# depg0213.net
KiCad netlist of a schematic drawn in Altium Designer
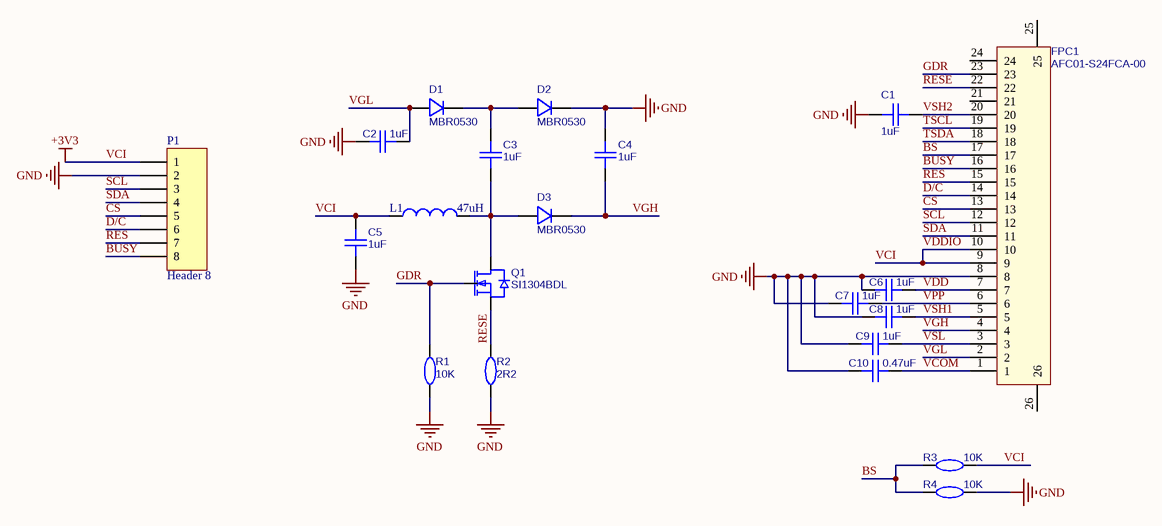
[diagram p0: depg0213.SchDoc]

(export (version "E")
  (design (tool "Eeschema 10.0.6"))
  (components
    (comp (ref "C1")
      (value "1uF")
      (footprint "C0603")
      (fields
        (field (name "BOM_SUPPLIER PART") "C325469")
        (field (name "BOM_MANUFACTURER PART") "CC0603GRNPO9BN200")
        (field (name "CONTRIBUTOR") "LCSC")
      )
      (libsource (lib "miscpcb") (part "CAP_0603"))
    )
    (comp (ref "C2")
      (value "1uF")
      (footprint "C0603")
      (fields
        (field (name "BOM_SUPPLIER PART") "C325469")
        (field (name "BOM_MANUFACTURER PART") "CC0603GRNPO9BN200")
        (field (name "CONTRIBUTOR") "LCSC")
      )
      (libsource (lib "miscpcb") (part "CAP_0603"))
    )
    (comp (ref "C3")
      (value "1uF")
      (footprint "C0603")
      (fields
        (field (name "BOM_SUPPLIER PART") "C325469")
        (field (name "BOM_MANUFACTURER PART") "CC0603GRNPO9BN200")
        (field (name "CONTRIBUTOR") "LCSC")
      )
      (libsource (lib "miscpcb") (part "CAP_0603"))
    )
    (comp (ref "C4")
      (value "1uF")
      (footprint "C0603")
      (fields
        (field (name "BOM_SUPPLIER PART") "C325469")
        (field (name "BOM_MANUFACTURER PART") "CC0603GRNPO9BN200")
        (field (name "CONTRIBUTOR") "LCSC")
      )
      (libsource (lib "miscpcb") (part "CAP_0603"))
    )
    (comp (ref "C5")
      (value "1uF")
      (footprint "C0603")
      (fields
        (field (name "BOM_SUPPLIER PART") "C325469")
        (field (name "BOM_MANUFACTURER PART") "CC0603GRNPO9BN200")
        (field (name "CONTRIBUTOR") "LCSC")
      )
      (libsource (lib "miscpcb") (part "CAP_0603"))
    )
    (comp (ref "C6")
      (value "1uF")
      (footprint "C0603")
      (fields
        (field (name "BOM_SUPPLIER PART") "C325469")
        (field (name "BOM_MANUFACTURER PART") "CC0603GRNPO9BN200")
        (field (name "CONTRIBUTOR") "LCSC")
      )
      (libsource (lib "miscpcb") (part "CAP_0603"))
    )
    (comp (ref "C7")
      (value "1uF")
      (footprint "C0603")
      (fields
        (field (name "BOM_SUPPLIER PART") "C325469")
        (field (name "BOM_MANUFACTURER PART") "CC0603GRNPO9BN200")
        (field (name "CONTRIBUTOR") "LCSC")
      )
      (libsource (lib "miscpcb") (part "CAP_0603"))
    )
    (comp (ref "C8")
      (value "1uF")
      (footprint "C0603")
      (fields
        (field (name "BOM_SUPPLIER PART") "C325469")
        (field (name "BOM_MANUFACTURER PART") "CC0603GRNPO9BN200")
        (field (name "CONTRIBUTOR") "LCSC")
      )
      (libsource (lib "miscpcb") (part "CAP_0603"))
    )
    (comp (ref "C9")
      (value "1uF")
      (footprint "C0603")
      (fields
        (field (name "BOM_SUPPLIER PART") "C325469")
        (field (name "BOM_MANUFACTURER PART") "CC0603GRNPO9BN200")
        (field (name "CONTRIBUTOR") "LCSC")
      )
      (libsource (lib "miscpcb") (part "CAP_0603"))
    )
    (comp (ref "C10")
      (value "0.47uF")
      (footprint "C0603")
      (fields
        (field (name "BOM_SUPPLIER PART") "C325469")
        (field (name "BOM_MANUFACTURER PART") "CC0603GRNPO9BN200")
        (field (name "CONTRIBUTOR") "LCSC")
      )
      (libsource (lib "miscpcb") (part "CAP_0603"))
    )
    (comp (ref "D1")
      (value "MBR0530")
      (footprint "SOD-123_L2.8-W1.8-LS3.7-RD")
      (description "C77336")
      (libsource (lib "miscpcb") (part "MBR0530"))
    )
    (comp (ref "D2")
      (value "MBR0530")
      (footprint "SOD-123_L2.8-W1.8-LS3.7-RD")
      (description "C77336")
      (libsource (lib "miscpcb") (part "MBR0530"))
    )
    (comp (ref "D3")
      (value "MBR0530")
      (footprint "SOD-123_L2.8-W1.8-LS3.7-RD")
      (description "C77336")
      (libsource (lib "miscpcb") (part "MBR0530"))
    )
    (comp (ref "FPC1")
      (value "AFC01-S24FCA-00")
      (footprint "FPC-SMD_P0.50-24P_FGS-XJ-H2.0")
      (description "C262669")
      (fields (field (name "CONTRIBUTOR") "LCSC"))
      (libsource (lib "miscpcb") (part "AFC01-S24FCA-00"))
    )
    (comp (ref "L1")
      (value "47uH")
      (footprint "IND-SMD_L3.0-W3.0_SMNR3015")
      (fields (field (name "PUBLISHER") "Altium Limited"))
      (libsource (lib "Miscellaneous Devices") (part "Inductor"))
    )
    (comp (ref "P1")
      (value "Header 8")
      (footprint "HDR1X8")
      (description "Header, 8-Pin")
      (fields (field (name "PUBLISHER") "Altium Limited"))
      (libsource (lib "Miscellaneous Connectors") (part "Header 8"))
    )
    (comp (ref "Q1")
      (value "SI1304BDL")
      (footprint "SC-70-3_L2.1-W1.3-P1.30-LS2.1-BR")
      (description "C710060")
      (fields (field (name "CONTRIBUTOR") "LCSC"))
      (libsource (lib "miscpcb") (part "SI1304BDL"))
    )
    (comp (ref "R1")
      (value "10K")
      (footprint "R0603")
      (fields
        (field (name "BOM_MANUFACTURER PART") "CR0603JA0301G")
        (field (name "BOM_SUPPLIER PART") "C101323")
      )
      (libsource (lib "miscpcb") (part "RES_0603"))
    )
    (comp (ref "R2")
      (value "2R2")
      (footprint "R0603")
      (fields
        (field (name "BOM_MANUFACTURER PART") "CR0603JA0301G")
        (field (name "BOM_SUPPLIER PART") "C101323")
      )
      (libsource (lib "miscpcb") (part "RES_0603"))
    )
    (comp (ref "R3")
      (value "10K")
      (footprint "R0603")
      (fields
        (field (name "BOM_MANUFACTURER PART") "CR0603JA0301G")
        (field (name "BOM_SUPPLIER PART") "C101323")
      )
      (libsource (lib "miscpcb") (part "RES_0603"))
    )
    (comp (ref "R4")
      (value "10K")
      (footprint "R0603")
      (fields
        (field (name "BOM_MANUFACTURER PART") "CR0603JA0301G")
        (field (name "BOM_SUPPLIER PART") "C101323")
      )
      (libsource (lib "miscpcb") (part "RES_0603"))
    )
  )
  (nets
    (net (code "1") (name "+3V3") (class "Default")
      (node (ref "C5") (pin "1") (pinfunction "1_1") (pintype "passive"))
      (node (ref "FPC1") (pin "10") (pinfunction "10_10") (pintype "passive"))
      (node (ref "FPC1") (pin "9") (pinfunction "9_9") (pintype "passive"))
      (node (ref "L1") (pin "1") (pinfunction "1_1") (pintype "passive"))
      (node (ref "P1") (pin "1") (pinfunction "1_1") (pintype "passive"))
      (node (ref "R3") (pin "2") (pinfunction "2_2") (pintype "passive"))
    )
    (net (code "2") (name "/BS") (class "Default")
      (node (ref "FPC1") (pin "17") (pinfunction "17_17") (pintype "passive"))
      (node (ref "R3") (pin "1") (pinfunction "1_1") (pintype "passive"))
      (node (ref "R4") (pin "1") (pinfunction "1_1") (pintype "passive"))
    )
    (net (code "3") (name "/BUSY") (class "Default")
      (node (ref "FPC1") (pin "16") (pinfunction "16_16") (pintype "passive"))
      (node (ref "P1") (pin "8") (pinfunction "8_8") (pintype "passive"))
    )
    (net (code "4") (name "/CS") (class "Default")
      (node (ref "FPC1") (pin "13") (pinfunction "13_13") (pintype "passive"))
      (node (ref "P1") (pin "5") (pinfunction "5_5") (pintype "passive"))
    )
    (net (code "5") (name "/D{slash}C") (class "Default")
      (node (ref "FPC1") (pin "14") (pinfunction "14_14") (pintype "passive"))
      (node (ref "P1") (pin "6") (pinfunction "6_6") (pintype "passive"))
    )
    (net (code "6") (name "/GDR") (class "Default")
      (node (ref "FPC1") (pin "23") (pinfunction "23_23") (pintype "passive"))
      (node (ref "Q1") (pin "1") (pinfunction "G_1") (pintype "passive"))
      (node (ref "R1") (pin "1") (pinfunction "1_1") (pintype "passive"))
    )
    (net (code "7") (name "/RES") (class "Default")
      (node (ref "FPC1") (pin "15") (pinfunction "15_15") (pintype "passive"))
      (node (ref "P1") (pin "7") (pinfunction "7_7") (pintype "passive"))
    )
    (net (code "8") (name "/RESE") (class "Default")
      (node (ref "FPC1") (pin "22") (pinfunction "22_22") (pintype "passive"))
      (node (ref "Q1") (pin "2") (pinfunction "S_2") (pintype "passive"))
      (node (ref "R2") (pin "1") (pinfunction "1_1") (pintype "passive"))
    )
    (net (code "9") (name "/SCL") (class "Default")
      (node (ref "FPC1") (pin "12") (pinfunction "12_12") (pintype "passive"))
      (node (ref "P1") (pin "3") (pinfunction "3_3") (pintype "passive"))
    )
    (net (code "10") (name "/SDA") (class "Default")
      (node (ref "FPC1") (pin "11") (pinfunction "11_11") (pintype "passive"))
      (node (ref "P1") (pin "4") (pinfunction "4_4") (pintype "passive"))
    )
    (net (code "11") (name "/TSCL") (class "Default")
      (node (ref "FPC1") (pin "19") (pinfunction "19_19") (pintype "passive"))
    )
    (net (code "12") (name "/TSDA") (class "Default")
      (node (ref "FPC1") (pin "18") (pinfunction "18_18") (pintype "passive"))
    )
    (net (code "13") (name "/VCOM") (class "Default")
      (node (ref "C10") (pin "2") (pinfunction "2_2") (pintype "passive"))
      (node (ref "FPC1") (pin "1") (pinfunction "1_1") (pintype "passive"))
    )
    (net (code "14") (name "/VDD") (class "Default")
      (node (ref "C6") (pin "2") (pinfunction "2_2") (pintype "passive"))
      (node (ref "FPC1") (pin "7") (pinfunction "7_7") (pintype "passive"))
    )
    (net (code "15") (name "/VGH") (class "Default")
      (node (ref "C4") (pin "2") (pinfunction "2_2") (pintype "passive"))
      (node (ref "D3") (pin "1") (pinfunction "C_1") (pintype "passive"))
      (node (ref "FPC1") (pin "4") (pinfunction "4_4") (pintype "passive"))
    )
    (net (code "16") (name "/VGL") (class "Default")
      (node (ref "C2") (pin "1") (pinfunction "1_1") (pintype "passive"))
      (node (ref "D1") (pin "2") (pinfunction "A_2") (pintype "passive"))
      (node (ref "FPC1") (pin "2") (pinfunction "2_2") (pintype "passive"))
    )
    (net (code "17") (name "/VPP") (class "Default")
      (node (ref "C7") (pin "2") (pinfunction "2_2") (pintype "passive"))
      (node (ref "FPC1") (pin "6") (pinfunction "6_6") (pintype "passive"))
    )
    (net (code "18") (name "/VSH1") (class "Default")
      (node (ref "C8") (pin "2") (pinfunction "2_2") (pintype "passive"))
      (node (ref "FPC1") (pin "5") (pinfunction "5_5") (pintype "passive"))
    )
    (net (code "19") (name "/VSH2") (class "Default")
      (node (ref "C1") (pin "2") (pinfunction "2_2") (pintype "passive"))
      (node (ref "FPC1") (pin "20") (pinfunction "20_20") (pintype "passive"))
    )
    (net (code "20") (name "/VSL") (class "Default")
      (node (ref "C9") (pin "2") (pinfunction "2_2") (pintype "passive"))
      (node (ref "FPC1") (pin "3") (pinfunction "3_3") (pintype "passive"))
    )
    (net (code "21") (name "GND") (class "Default")
      (node (ref "C1") (pin "1") (pinfunction "1_1") (pintype "passive"))
      (node (ref "C10") (pin "1") (pinfunction "1_1") (pintype "passive"))
      (node (ref "C2") (pin "2") (pinfunction "2_2") (pintype "passive"))
      (node (ref "C4") (pin "1") (pinfunction "1_1") (pintype "passive"))
      (node (ref "C5") (pin "2") (pinfunction "2_2") (pintype "passive"))
      (node (ref "C6") (pin "1") (pinfunction "1_1") (pintype "passive"))
      (node (ref "C7") (pin "1") (pinfunction "1_1") (pintype "passive"))
      (node (ref "C8") (pin "1") (pinfunction "1_1") (pintype "passive"))
      (node (ref "C9") (pin "1") (pinfunction "1_1") (pintype "passive"))
      (node (ref "D2") (pin "1") (pinfunction "C_1") (pintype "passive"))
      (node (ref "FPC1") (pin "8") (pinfunction "8_8") (pintype "passive"))
      (node (ref "P1") (pin "2") (pinfunction "2_2") (pintype "passive"))
      (node (ref "R1") (pin "2") (pinfunction "2_2") (pintype "passive"))
      (node (ref "R2") (pin "2") (pinfunction "2_2") (pintype "passive"))
      (node (ref "R4") (pin "2") (pinfunction "2_2") (pintype "passive"))
    )
    (net (code "22") (name "Net-(D1-C)") (class "Default")
      (node (ref "C3") (pin "1") (pinfunction "1_1") (pintype "passive"))
      (node (ref "D1") (pin "1") (pinfunction "C_1") (pintype "passive"))
      (node (ref "D2") (pin "2") (pinfunction "A_2") (pintype "passive"))
    )
    (net (code "23") (name "Net-(D3-A)") (class "Default")
      (node (ref "C3") (pin "2") (pinfunction "2_2") (pintype "passive"))
      (node (ref "D3") (pin "2") (pinfunction "A_2") (pintype "passive"))
      (node (ref "L1") (pin "2") (pinfunction "2_2") (pintype "passive"))
      (node (ref "Q1") (pin "3") (pinfunction "D_3") (pintype "passive"))
    )
    (net (code "24") (name "unconnected-(FPC1-Pad21)") (class "Default")
      (node (ref "FPC1") (pin "21") (pinfunction "21_21") (pintype "passive"))
    )
    (net (code "25") (name "unconnected-(FPC1-Pad24)") (class "Default")
      (node (ref "FPC1") (pin "24") (pinfunction "24_24") (pintype "passive"))
    )
    (net (code "26") (name "unconnected-(FPC1-Pad25)") (class "Default")
      (node (ref "FPC1") (pin "25") (pinfunction "25_25") (pintype "passive"))
    )
    (net (code "27") (name "unconnected-(FPC1-Pad26)") (class "Default")
      (node (ref "FPC1") (pin "26") (pinfunction "26_26") (pintype "passive"))
    )
  )
)
